# Sheet1.net
KiCad netlist of a schematic drawn in Altium Designer
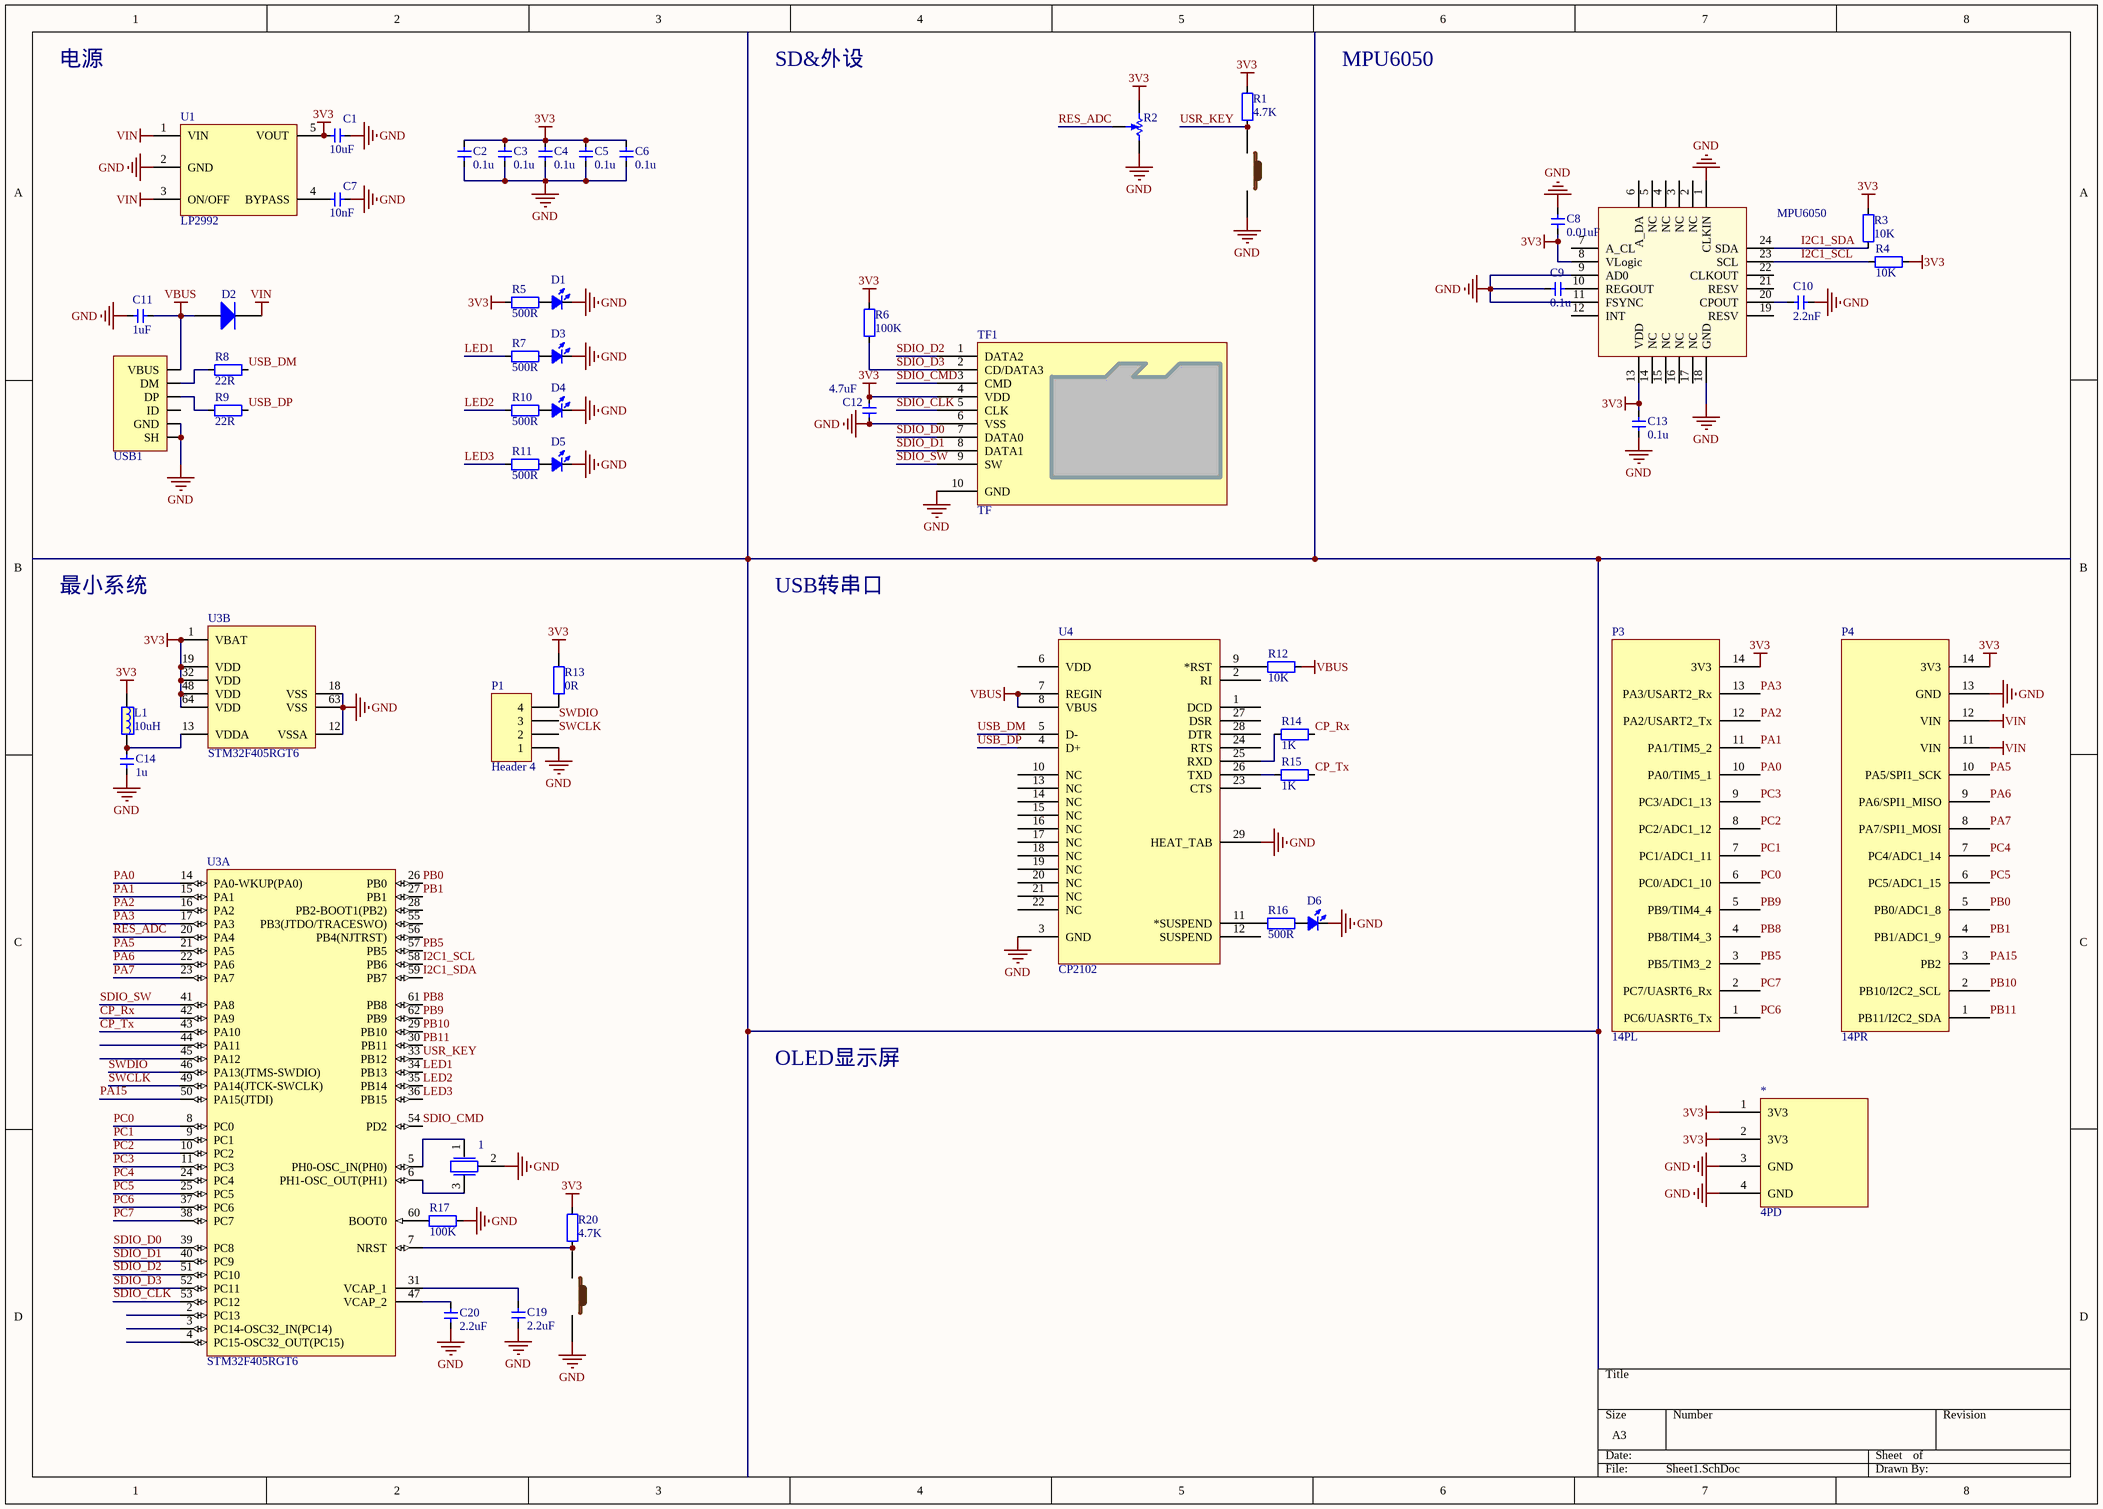
[diagram p0: Sheet1.SchDoc]

(export (version "E")
  (design (tool "Eeschema 10.0.6"))
  (components
    (comp (ref "*") (value "4PD") (footprint "4P") (libsource (lib "mLib") (part "4PD")))
    (comp (ref "1")
      (value "晶振-3Pin")
      (footprint "晶振-3P")
      (description "村田贴片")
      (libsource (lib "mLib") (part "晶振-3Pin"))
    )
    (comp (ref "C1")
      (value "10uF")
      (footprint "mLib:0603-CAP")
      (description "Capacitor")
      (libsource (lib "mLib") (part "电容-0603"))
    )
    (comp (ref "C2")
      (value "0.1u")
      (footprint "mLib:0603-CAP")
      (description "Capacitor")
      (fields (field (name "Comment") "0.1uF"))
      (libsource (lib "mLib") (part "电容-0603"))
    )
    (comp (ref "C3")
      (value "0.1u")
      (footprint "mLib:0603-CAP")
      (description "Capacitor")
      (fields (field (name "Comment") "0.1uF"))
      (libsource (lib "mLib") (part "电容-0603"))
    )
    (comp (ref "C4")
      (value "0.1u")
      (footprint "mLib:0603-CAP")
      (description "Capacitor")
      (fields (field (name "Comment") "0.1uF"))
      (libsource (lib "mLib") (part "电容-0603"))
    )
    (comp (ref "C5")
      (value "0.1u")
      (footprint "mLib:0603-CAP")
      (description "Capacitor")
      (fields (field (name "Comment") "电容-0603"))
      (libsource (lib "mLib") (part "电容-0603"))
    )
    (comp (ref "C6")
      (value "0.1u")
      (footprint "mLib:0603-CAP")
      (description "Capacitor")
      (fields (field (name "Comment") "0.1uF"))
      (libsource (lib "mLib") (part "电容-0603"))
    )
    (comp (ref "C7")
      (value "10nF")
      (footprint "mLib:0603-CAP")
      (description "Capacitor")
      (libsource (lib "mLib") (part "电容-0603"))
    )
    (comp (ref "C8")
      (value "0.01uF")
      (footprint "mLib:0603-CAP")
      (description "Capacitor")
      (libsource (lib "mLib") (part "电容-0603"))
    )
    (comp (ref "C9")
      (value "0.1u")
      (footprint "mLib:0603-CAP")
      (description "Capacitor")
      (fields (field (name "Comment") "0.1uF"))
      (libsource (lib "mLib") (part "电容-0603"))
    )
    (comp (ref "C10")
      (value "2.2nF")
      (footprint "mLib:0603-CAP")
      (description "Capacitor")
      (libsource (lib "mLib") (part "电容-0603"))
    )
    (comp (ref "C11")
      (value "1uF")
      (footprint "mLib:0603-CAP")
      (description "Capacitor")
      (libsource (lib "mLib") (part "电容-0603"))
    )
    (comp (ref "C12")
      (value "4.7uF")
      (footprint "mLib:0603-CAP")
      (description "Capacitor")
      (libsource (lib "mLib") (part "电容-0603"))
    )
    (comp (ref "C13")
      (value "0.1u")
      (footprint "mLib:0603-CAP")
      (description "Capacitor")
      (fields (field (name "Comment") "0.1uF"))
      (libsource (lib "mLib") (part "电容-0603"))
    )
    (comp (ref "C14")
      (value "1u")
      (footprint "mLib:0603-CAP")
      (description "Capacitor")
      (fields (field (name "Comment") "1uF"))
      (libsource (lib "mLib") (part "电容-0603"))
    )
    (comp (ref "C19")
      (value "2.2uF")
      (footprint "mLib:0603-CAP")
      (description "Capacitor")
      (libsource (lib "mLib") (part "电容-0603"))
    )
    (comp (ref "C20")
      (value "2.2uF")
      (footprint "mLib:0603-CAP")
      (description "Capacitor")
      (libsource (lib "mLib") (part "电容-0603"))
    )
    (comp (ref "D1")
      (value "LED-0603")
      (footprint "mLib:0603-LED-BLUE")
      (description "LED")
      (libsource (lib "mLib") (part "LED-0603"))
    )
    (comp (ref "D2")
      (value "二极管-5819W")
      (footprint "SOD-123")
      (description "40V")
      (libsource (lib "mLib") (part "二极管-5819W"))
    )
    (comp (ref "D3")
      (value "LED-0603")
      (footprint "mLib:0603-LED-BLUE")
      (description "LED")
      (libsource (lib "mLib") (part "LED-0603"))
    )
    (comp (ref "D4")
      (value "LED-0603")
      (footprint "mLib:0603-LED-BLUE")
      (description "LED")
      (libsource (lib "mLib") (part "LED-0603"))
    )
    (comp (ref "D5")
      (value "LED-0603")
      (footprint "mLib:0603-LED-BLUE")
      (description "LED")
      (libsource (lib "mLib") (part "LED-0603"))
    )
    (comp (ref "D6")
      (value "LED-0603")
      (footprint "mLib:0603-LED-BLUE")
      (description "LED")
      (libsource (lib "mLib") (part "LED-0603"))
    )
    (comp (ref "L1")
      (value "10uH")
      (footprint "0805-L")
      (description "磁珠")
      (libsource (lib "mLib") (part "电感-0805"))
    )
    (comp (ref "P1")
      (value "Header 4")
      (footprint "HDR1X4")
      (description "Header, 4-Pin")
      (fields (field (name "PUBLISHER") "Altium Limited"))
      (libsource (lib "Miscellaneous Connectors") (part "Header 4"))
    )
    (comp (ref "P3") (value "14PL") (footprint "14P") (libsource (lib "mLib") (part "14PL")))
    (comp (ref "P4") (value "14PR") (footprint "14P") (libsource (lib "mLib") (part "14PR")))
    (comp (ref "R1")
      (value "4.7K")
      (footprint "mLib:0603-RES")
      (description "Resistor")
      (libsource (lib "mLib") (part "电阻-0603"))
    )
    (comp (ref "R2")
      (value "电位器-贴片")
      (footprint "贴片电位器 3*3")
      (fields (field (name "PUBLISHER") "Altium Limited"))
      (libsource (lib "mLib") (part "电位器-贴片"))
    )
    (comp (ref "R3")
      (value "10K")
      (footprint "mLib:0603-RES")
      (description "Resistor")
      (libsource (lib "mLib") (part "电阻-0603"))
    )
    (comp (ref "R4")
      (value "10K")
      (footprint "mLib:0603-RES")
      (description "Resistor")
      (libsource (lib "") (part "电阻-0603_1"))
    )
    (comp (ref "R5")
      (value "500R")
      (footprint "mLib:0603-RES")
      (description "Resistor")
      (libsource (lib "") (part "电阻-0603_1"))
    )
    (comp (ref "R6")
      (value "100K")
      (footprint "mLib:0603-RES")
      (description "Resistor")
      (libsource (lib "mLib") (part "电阻-0603"))
    )
    (comp (ref "R7")
      (value "500R")
      (footprint "mLib:0603-RES")
      (description "Resistor")
      (libsource (lib "") (part "电阻-0603_1"))
    )
    (comp (ref "R8")
      (value "22R")
      (footprint "mLib:0603-RES")
      (description "Resistor")
      (libsource (lib "") (part "电阻-0603_1"))
    )
    (comp (ref "R9")
      (value "22R")
      (footprint "mLib:0603-RES")
      (description "Resistor")
      (libsource (lib "") (part "电阻-0603_1"))
    )
    (comp (ref "R10")
      (value "500R")
      (footprint "mLib:0603-RES")
      (description "Resistor")
      (libsource (lib "") (part "电阻-0603_1"))
    )
    (comp (ref "R11")
      (value "500R")
      (footprint "mLib:0603-RES")
      (description "Resistor")
      (libsource (lib "") (part "电阻-0603_1"))
    )
    (comp (ref "R12")
      (value "10K")
      (footprint "mLib:0603-RES")
      (description "Resistor")
      (libsource (lib "") (part "电阻-0603_1"))
    )
    (comp (ref "R13")
      (value "0R")
      (footprint "0402-0R")
      (description "Resistor")
      (fields (field (name "Comment") "电阻-0R") (field (name "PUBLISHER") "Altium Limited"))
      (libsource (lib "mLib") (part "电阻-0R"))
    )
    (comp (ref "R14")
      (value "1K")
      (footprint "mLib:0603-RES")
      (description "Resistor")
      (libsource (lib "") (part "电阻-0603_1"))
    )
    (comp (ref "R15")
      (value "1K")
      (footprint "mLib:0603-RES")
      (description "Resistor")
      (libsource (lib "") (part "电阻-0603_1"))
    )
    (comp (ref "R16")
      (value "500R")
      (footprint "mLib:0603-RES")
      (description "Resistor")
      (libsource (lib "") (part "电阻-0603_1"))
    )
    (comp (ref "R17")
      (value "100K")
      (footprint "mLib:0603-RES")
      (description "Resistor")
      (libsource (lib "") (part "电阻-0603_1"))
    )
    (comp (ref "R20")
      (value "4.7K")
      (footprint "mLib:0603-RES")
      (description "Resistor")
      (libsource (lib "mLib") (part "电阻-0603"))
    )
    (comp (ref "TF1")
      (value "TF")
      (footprint "TF-SOCKET")
      (description "8脚自弹")
      (libsource (lib "mLib") (part "TF卡座"))
    )
    (comp (ref "U1")
      (value "LP2992")
      (footprint "SOT23-5")
      (description "LDO")
      (libsource (lib "mLib") (part "LP2992"))
    )
    (comp (ref "U2")
      (value "MPU6050")
      (footprint "QFN-24")
      (description "六轴传感器")
      (libsource (lib "mLib") (part "MPU6050"))
    )
    (comp (ref "U3")
      (value "STM32F405RGT6")
      (footprint "LQFP-64_N")
      (description "MCU+FPU")
      (libsource (lib "mLib") (part "STM32F405RGT6"))
    )
    (comp (ref "U4")
      (value "CP2102")
      (footprint "QFN-28")
      (description "USB转TTL")
      (libsource (lib "mLib") (part "CP2102"))
    )
    (comp (ref "USB1")
      (value "USB-Micro")
      (footprint "mLib:USB_Micro-AB")
      (description "USB")
      (libsource (lib "mLib") (part "USB-Micro"))
    )
    (comp (ref "按键1")
      (value "Reset")
      (footprint "SW-KEY2")
      (description "贴片轻触")
      (libsource (lib "mLib") (part "按键-4Pin"))
    )
    (comp (ref "按键2")
      (value "Reset")
      (footprint "SW-KEY2")
      (description "贴片轻触")
      (libsource (lib "mLib") (part "按键-4Pin"))
    )
  )
  (nets
    (net (code "1") (name "/CP_Rx") (class "Default")
      (node (ref "R14") (pin "2") (pinfunction "2_2") (pintype "passive"))
      (node (ref "U3") (pin "42") (pinfunction "PA9_42") (pintype "bidirectional"))
    )
    (net (code "2") (name "/CP_Tx") (class "Default")
      (node (ref "R15") (pin "2") (pinfunction "2_2") (pintype "passive"))
      (node (ref "U3") (pin "43") (pinfunction "PA10_43") (pintype "bidirectional"))
    )
    (net (code "3") (name "/I2C1_SCL") (class "Default")
      (node (ref "R4") (pin "1") (pinfunction "1_1") (pintype "passive"))
      (node (ref "U2") (pin "23") (pinfunction "SCL_23") (pintype "passive"))
      (node (ref "U3") (pin "58") (pinfunction "PB6_58") (pintype "bidirectional"))
    )
    (net (code "4") (name "/I2C1_SDA") (class "Default")
      (node (ref "R3") (pin "1") (pinfunction "1_1") (pintype "passive"))
      (node (ref "U2") (pin "24") (pinfunction "SDA_24") (pintype "passive"))
      (node (ref "U3") (pin "59") (pinfunction "PB7_59") (pintype "bidirectional"))
    )
    (net (code "5") (name "/LED1") (class "Default")
      (node (ref "R7") (pin "1") (pinfunction "1_1") (pintype "passive"))
      (node (ref "U3") (pin "34") (pinfunction "PB13_34") (pintype "bidirectional"))
    )
    (net (code "6") (name "/LED2") (class "Default")
      (node (ref "R10") (pin "1") (pinfunction "1_1") (pintype "passive"))
      (node (ref "U3") (pin "35") (pinfunction "PB14_35") (pintype "bidirectional"))
    )
    (net (code "7") (name "/LED3") (class "Default")
      (node (ref "R11") (pin "1") (pinfunction "1_1") (pintype "passive"))
      (node (ref "U3") (pin "36") (pinfunction "PB15_36") (pintype "bidirectional"))
    )
    (net (code "8") (name "/PA0") (class "Default")
      (node (ref "P3") (pin "10") (pinfunction "PA0/TIM5_1_10") (pintype "passive"))
      (node (ref "U3") (pin "14") (pinfunction "PA0-WKUP(PA0)_14") (pintype "bidirectional"))
    )
    (net (code "9") (name "/PA1") (class "Default")
      (node (ref "P3") (pin "11") (pinfunction "PA1/TIM5_2_11") (pintype "passive"))
      (node (ref "U3") (pin "15") (pinfunction "PA1_15") (pintype "bidirectional"))
    )
    (net (code "10") (name "/PA2") (class "Default")
      (node (ref "P3") (pin "12") (pinfunction "PA2/USART2_Tx_12") (pintype "passive"))
      (node (ref "U3") (pin "16") (pinfunction "PA2_16") (pintype "bidirectional"))
    )
    (net (code "11") (name "/PA3") (class "Default")
      (node (ref "P3") (pin "13") (pinfunction "PA3/USART2_Rx_13") (pintype "passive"))
      (node (ref "U3") (pin "17") (pinfunction "PA3_17") (pintype "bidirectional"))
    )
    (net (code "12") (name "/PA5") (class "Default")
      (node (ref "P4") (pin "10") (pinfunction "PA5/SPI1_SCK_10") (pintype "passive"))
      (node (ref "U3") (pin "21") (pinfunction "PA5_21") (pintype "bidirectional"))
    )
    (net (code "13") (name "/PA6") (class "Default")
      (node (ref "P4") (pin "9") (pinfunction "PA6/SPI1_MISO_9") (pintype "passive"))
      (node (ref "U3") (pin "22") (pinfunction "PA6_22") (pintype "bidirectional"))
    )
    (net (code "14") (name "/PA7") (class "Default")
      (node (ref "P4") (pin "8") (pinfunction "PA7/SPI1_MOSI_8") (pintype "passive"))
      (node (ref "U3") (pin "23") (pinfunction "PA7_23") (pintype "bidirectional"))
    )
    (net (code "15") (name "/PA15") (class "Default")
      (node (ref "P4") (pin "3") (pinfunction "PB2_3") (pintype "passive"))
      (node (ref "U3") (pin "50") (pinfunction "PA15(JTDI)_50") (pintype "bidirectional"))
    )
    (net (code "16") (name "/PB0") (class "Default")
      (node (ref "P4") (pin "5") (pinfunction "PB0/ADC1_8_5") (pintype "passive"))
      (node (ref "U3") (pin "26") (pinfunction "PB0_26") (pintype "bidirectional"))
    )
    (net (code "17") (name "/PB1") (class "Default")
      (node (ref "P4") (pin "4") (pinfunction "PB1/ADC1_9_4") (pintype "passive"))
      (node (ref "U3") (pin "27") (pinfunction "PB1_27") (pintype "bidirectional"))
    )
    (net (code "18") (name "/PB5") (class "Default")
      (node (ref "P3") (pin "3") (pinfunction "PB5/TIM3_2_3") (pintype "passive"))
      (node (ref "U3") (pin "57") (pinfunction "PB5_57") (pintype "bidirectional"))
    )
    (net (code "19") (name "/PB8") (class "Default")
      (node (ref "P3") (pin "4") (pinfunction "PB8/TIM4_3_4") (pintype "passive"))
      (node (ref "U3") (pin "61") (pinfunction "PB8_61") (pintype "bidirectional"))
    )
    (net (code "20") (name "/PB9") (class "Default")
      (node (ref "P3") (pin "5") (pinfunction "PB9/TIM4_4_5") (pintype "passive"))
      (node (ref "U3") (pin "62") (pinfunction "PB9_62") (pintype "bidirectional"))
    )
    (net (code "21") (name "/PB10") (class "Default")
      (node (ref "P4") (pin "2") (pinfunction "PB10/I2C2_SCL_2") (pintype "passive"))
      (node (ref "U3") (pin "29") (pinfunction "PB10_29") (pintype "bidirectional"))
    )
    (net (code "22") (name "/PB11") (class "Default")
      (node (ref "P4") (pin "1") (pinfunction "PB11/I2C2_SDA_1") (pintype "passive"))
      (node (ref "U3") (pin "30") (pinfunction "PB11_30") (pintype "bidirectional"))
    )
    (net (code "23") (name "/PC0") (class "Default")
      (node (ref "P3") (pin "6") (pinfunction "PC0/ADC1_10_6") (pintype "passive"))
      (node (ref "U3") (pin "8") (pinfunction "PC0_8") (pintype "bidirectional"))
    )
    (net (code "24") (name "/PC1") (class "Default")
      (node (ref "P3") (pin "7") (pinfunction "PC1/ADC1_11_7") (pintype "passive"))
      (node (ref "U3") (pin "9") (pinfunction "PC1_9") (pintype "bidirectional"))
    )
    (net (code "25") (name "/PC2") (class "Default")
      (node (ref "P3") (pin "8") (pinfunction "PC2/ADC1_12_8") (pintype "passive"))
      (node (ref "U3") (pin "10") (pinfunction "PC2_10") (pintype "bidirectional"))
    )
    (net (code "26") (name "/PC3") (class "Default")
      (node (ref "P3") (pin "9") (pinfunction "PC3/ADC1_13_9") (pintype "passive"))
      (node (ref "U3") (pin "11") (pinfunction "PC3_11") (pintype "bidirectional"))
    )
    (net (code "27") (name "/PC4") (class "Default")
      (node (ref "P4") (pin "7") (pinfunction "PC4/ADC1_14_7") (pintype "passive"))
      (node (ref "U3") (pin "24") (pinfunction "PC4_24") (pintype "bidirectional"))
    )
    (net (code "28") (name "/PC5") (class "Default")
      (node (ref "P4") (pin "6") (pinfunction "PC5/ADC1_15_6") (pintype "passive"))
      (node (ref "U3") (pin "25") (pinfunction "PC5_25") (pintype "bidirectional"))
    )
    (net (code "29") (name "/PC6") (class "Default")
      (node (ref "P3") (pin "1") (pinfunction "PC6/UASRT6_Tx_1") (pintype "passive"))
      (node (ref "U3") (pin "37") (pinfunction "PC6_37") (pintype "bidirectional"))
    )
    (net (code "30") (name "/PC7") (class "Default")
      (node (ref "P3") (pin "2") (pinfunction "PC7/UASRT6_Rx_2") (pintype "passive"))
      (node (ref "U3") (pin "38") (pinfunction "PC7_38") (pintype "bidirectional"))
    )
    (net (code "31") (name "/RES_ADC") (class "Default")
      (node (ref "R2") (pin "3") (pinfunction "W_3") (pintype "passive"))
      (node (ref "U3") (pin "20") (pinfunction "PA4_20") (pintype "bidirectional"))
    )
    (net (code "32") (name "/SDIO_CLK") (class "Default")
      (node (ref "TF1") (pin "5") (pinfunction "CLK_5") (pintype "passive"))
      (node (ref "U3") (pin "53") (pinfunction "PC12_53") (pintype "bidirectional"))
    )
    (net (code "33") (name "/SDIO_CMD") (class "Default")
      (node (ref "TF1") (pin "3") (pinfunction "CMD_3") (pintype "passive"))
      (node (ref "U3") (pin "54") (pinfunction "PD2_54") (pintype "bidirectional"))
    )
    (net (code "34") (name "/SDIO_D0") (class "Default")
      (node (ref "TF1") (pin "7") (pinfunction "DATA0_7") (pintype "passive"))
      (node (ref "U3") (pin "39") (pinfunction "PC8_39") (pintype "bidirectional"))
    )
    (net (code "35") (name "/SDIO_D1") (class "Default")
      (node (ref "TF1") (pin "8") (pinfunction "DATA1_8") (pintype "passive"))
      (node (ref "U3") (pin "40") (pinfunction "PC9_40") (pintype "bidirectional"))
    )
    (net (code "36") (name "/SDIO_D2") (class "Default")
      (node (ref "TF1") (pin "1") (pinfunction "DATA2_1") (pintype "passive"))
      (node (ref "U3") (pin "51") (pinfunction "PC10_51") (pintype "bidirectional"))
    )
    (net (code "37") (name "/SDIO_D3") (class "Default")
      (node (ref "R6") (pin "1") (pinfunction "1_1") (pintype "passive"))
      (node (ref "TF1") (pin "2") (pinfunction "CD/DATA3_2") (pintype "passive"))
      (node (ref "U3") (pin "52") (pinfunction "PC11_52") (pintype "bidirectional"))
    )
    (net (code "38") (name "/SDIO_SW") (class "Default")
      (node (ref "TF1") (pin "9") (pinfunction "SW_9") (pintype "passive"))
      (node (ref "U3") (pin "41") (pinfunction "PA8_41") (pintype "bidirectional"))
    )
    (net (code "39") (name "/SWCLK") (class "Default")
      (node (ref "P1") (pin "2") (pinfunction "2_2") (pintype "passive"))
      (node (ref "U3") (pin "49") (pinfunction "PA14(JTCK-SWCLK)_49") (pintype "bidirectional"))
    )
    (net (code "40") (name "/SWDIO") (class "Default")
      (node (ref "P1") (pin "3") (pinfunction "3_3") (pintype "passive"))
      (node (ref "U3") (pin "46") (pinfunction "PA13(JTMS-SWDIO)_46") (pintype "bidirectional"))
    )
    (net (code "41") (name "/USB_DM") (class "Default")
      (node (ref "R8") (pin "2") (pinfunction "2_2") (pintype "passive"))
      (node (ref "U4") (pin "5") (pinfunction "D-_5") (pintype "passive"))
    )
    (net (code "42") (name "/USB_DP") (class "Default")
      (node (ref "R9") (pin "2") (pinfunction "2_2") (pintype "passive"))
      (node (ref "U4") (pin "4") (pinfunction "D+_4") (pintype "passive"))
    )
    (net (code "43") (name "/USR_KEY") (class "Default")
      (node (ref "R1") (pin "1") (pinfunction "1_1") (pintype "passive"))
      (node (ref "U3") (pin "33") (pinfunction "PB12_33") (pintype "bidirectional"))
      (node (ref "按键1") (pin "1") (pinfunction "1_1") (pintype "passive"))
    )
    (net (code "44") (name "3V3") (class "Default")
      (node (ref "*") (pin "1") (pinfunction "3V3_1") (pintype "passive"))
      (node (ref "*") (pin "2") (pinfunction "3V3_2") (pintype "passive"))
      (node (ref "C1") (pin "2") (pinfunction "2_2") (pintype "passive"))
      (node (ref "C12") (pin "1") (pinfunction "1_1") (pintype "passive"))
      (node (ref "C13") (pin "2") (pinfunction "2_2") (pintype "passive"))
      (node (ref "C2") (pin "1") (pinfunction "1_1") (pintype "passive"))
      (node (ref "C3") (pin "1") (pinfunction "1_1") (pintype "passive"))
      (node (ref "C4") (pin "1") (pinfunction "1_1") (pintype "passive"))
      (node (ref "C5") (pin "1") (pinfunction "1_1") (pintype "passive"))
      (node (ref "C6") (pin "1") (pinfunction "1_1") (pintype "passive"))
      (node (ref "C8") (pin "2") (pinfunction "2_2") (pintype "passive"))
      (node (ref "L1") (pin "1") (pintype "passive"))
      (node (ref "P3") (pin "14") (pinfunction "3V3_14") (pintype "passive"))
      (node (ref "P4") (pin "14") (pinfunction "3V3_14") (pintype "passive"))
      (node (ref "R1") (pin "2") (pinfunction "2_2") (pintype "passive"))
      (node (ref "R13") (pin "2") (pinfunction "2_2") (pintype "passive"))
      (node (ref "R2") (pin "2") (pinfunction "-_2") (pintype "passive"))
      (node (ref "R20") (pin "2") (pinfunction "2_2") (pintype "passive"))
      (node (ref "R3") (pin "2") (pinfunction "2_2") (pintype "passive"))
      (node (ref "R4") (pin "2") (pinfunction "2_2") (pintype "passive"))
      (node (ref "R5") (pin "1") (pinfunction "1_1") (pintype "passive"))
      (node (ref "R6") (pin "2") (pinfunction "2_2") (pintype "passive"))
      (node (ref "TF1") (pin "4") (pinfunction "VDD_4") (pintype "passive"))
      (node (ref "U1") (pin "5") (pinfunction "VOUT_5") (pintype "passive"))
      (node (ref "U2") (pin "13") (pinfunction "VDD_13") (pintype "passive"))
      (node (ref "U2") (pin "8") (pinfunction "VLogic_8") (pintype "passive"))
      (node (ref "U3") (pin "1") (pinfunction "VBAT_1") (pintype "power_in"))
      (node (ref "U3") (pin "19") (pinfunction "VDD_19") (pintype "power_in"))
      (node (ref "U3") (pin "32") (pinfunction "VDD_32") (pintype "power_in"))
      (node (ref "U3") (pin "48") (pinfunction "VDD_48") (pintype "power_in"))
      (node (ref "U3") (pin "64") (pinfunction "VDD_64") (pintype "power_in"))
    )
    (net (code "45") (name "GND") (class "Default")
      (node (ref "*") (pin "3") (pinfunction "GND_3") (pintype "passive"))
      (node (ref "*") (pin "4") (pinfunction "GND_4") (pintype "passive"))
      (node (ref "1") (pin "2") (pinfunction "2_2") (pintype "passive"))
      (node (ref "C1") (pin "1") (pinfunction "1_1") (pintype "passive"))
      (node (ref "C10") (pin "2") (pinfunction "2_2") (pintype "passive"))
      (node (ref "C11") (pin "1") (pinfunction "1_1") (pintype "passive"))
      (node (ref "C12") (pin "2") (pinfunction "2_2") (pintype "passive"))
      (node (ref "C13") (pin "1") (pinfunction "1_1") (pintype "passive"))
      (node (ref "C14") (pin "1") (pinfunction "1_1") (pintype "passive"))
      (node (ref "C19") (pin "1") (pinfunction "1_1") (pintype "passive"))
      (node (ref "C2") (pin "2") (pinfunction "2_2") (pintype "passive"))
      (node (ref "C20") (pin "1") (pinfunction "1_1") (pintype "passive"))
      (node (ref "C3") (pin "2") (pinfunction "2_2") (pintype "passive"))
      (node (ref "C4") (pin "2") (pinfunction "2_2") (pintype "passive"))
      (node (ref "C5") (pin "2") (pinfunction "2_2") (pintype "passive"))
      (node (ref "C6") (pin "2") (pinfunction "2_2") (pintype "passive"))
      (node (ref "C7") (pin "1") (pinfunction "1_1") (pintype "passive"))
      (node (ref "C8") (pin "1") (pinfunction "1_1") (pintype "passive"))
      (node (ref "C9") (pin "1") (pinfunction "1_1") (pintype "passive"))
      (node (ref "D1") (pin "2") (pinfunction "K_2") (pintype "passive"))
      (node (ref "D3") (pin "2") (pinfunction "K_2") (pintype "passive"))
      (node (ref "D4") (pin "2") (pinfunction "K_2") (pintype "passive"))
      (node (ref "D5") (pin "2") (pinfunction "K_2") (pintype "passive"))
      (node (ref "D6") (pin "2") (pinfunction "K_2") (pintype "passive"))
      (node (ref "P1") (pin "1") (pinfunction "1_1") (pintype "passive"))
      (node (ref "P4") (pin "13") (pinfunction "GND_13") (pintype "passive"))
      (node (ref "R17") (pin "2") (pinfunction "2_2") (pintype "passive"))
      (node (ref "R2") (pin "1") (pinfunction "+_1") (pintype "passive"))
      (node (ref "TF1") (pin "10") (pinfunction "GND_10") (pintype "passive"))
      (node (ref "TF1") (pin "6") (pinfunction "VSS_6") (pintype "passive"))
      (node (ref "U1") (pin "2") (pinfunction "GND_2") (pintype "passive"))
      (node (ref "U2") (pin "1") (pinfunction "CLKIN_1") (pintype "passive"))
      (node (ref "U2") (pin "11") (pinfunction "FSYNC_11") (pintype "passive"))
      (node (ref "U2") (pin "18") (pinfunction "GND_18") (pintype "passive"))
      (node (ref "U2") (pin "9") (pinfunction "AD0_9") (pintype "passive"))
      (node (ref "U3") (pin "12") (pinfunction "VSSA_12") (pintype "power_in"))
      (node (ref "U3") (pin "18") (pinfunction "VSS_18") (pintype "power_in"))
      (node (ref "U3") (pin "63") (pinfunction "VSS_63") (pintype "power_in"))
      (node (ref "U4") (pin "29") (pinfunction "HEAT_TAB_29") (pintype "passive"))
      (node (ref "U4") (pin "3") (pinfunction "GND_3") (pintype "passive"))
      (node (ref "USB1") (pin "0") (pinfunction "SH_0") (pintype "passive"))
      (node (ref "USB1") (pin "5") (pinfunction "GND_5") (pintype "passive"))
      (node (ref "按键1") (pin "2") (pinfunction "2_2") (pintype "passive"))
      (node (ref "按键2") (pin "2") (pinfunction "2_2") (pintype "passive"))
    )
    (net (code "46") (name "Net-(D1-A)") (class "Default")
      (node (ref "D1") (pin "1") (pinfunction "A_1") (pintype "passive"))
      (node (ref "R5") (pin "2") (pinfunction "2_2") (pintype "passive"))
    )
    (net (code "47") (name "Net-(D3-A)") (class "Default")
      (node (ref "D3") (pin "1") (pinfunction "A_1") (pintype "passive"))
      (node (ref "R7") (pin "2") (pinfunction "2_2") (pintype "passive"))
    )
    (net (code "48") (name "Net-(D4-A)") (class "Default")
      (node (ref "D4") (pin "1") (pinfunction "A_1") (pintype "passive"))
      (node (ref "R10") (pin "2") (pinfunction "2_2") (pintype "passive"))
    )
    (net (code "49") (name "Net-(D5-A)") (class "Default")
      (node (ref "D5") (pin "1") (pinfunction "A_1") (pintype "passive"))
      (node (ref "R11") (pin "2") (pinfunction "2_2") (pintype "passive"))
    )
    (net (code "50") (name "Net-(D6-A)") (class "Default")
      (node (ref "D6") (pin "1") (pinfunction "A_1") (pintype "passive"))
      (node (ref "R16") (pin "2") (pinfunction "2_2") (pintype "passive"))
    )
    (net (code "51") (name "Net-(P1-Pad4)") (class "Default")
      (node (ref "P1") (pin "4") (pinfunction "4_4") (pintype "passive"))
      (node (ref "R13") (pin "1") (pinfunction "1_1") (pintype "passive"))
    )
    (net (code "52") (name "Net-(U1-BYPASS)") (class "Default")
      (node (ref "C7") (pin "2") (pinfunction "2_2") (pintype "passive"))
      (node (ref "U1") (pin "4") (pinfunction "BYPASS_4") (pintype "passive"))
    )
    (net (code "53") (name "Net-(U2-CPOUT)") (class "Default")
      (node (ref "C10") (pin "1") (pinfunction "1_1") (pintype "passive"))
      (node (ref "U2") (pin "20") (pinfunction "CPOUT_20") (pintype "passive"))
    )
    (net (code "54") (name "Net-(U2-REGOUT)") (class "Default")
      (node (ref "C9") (pin "2") (pinfunction "2_2") (pintype "passive"))
      (node (ref "U2") (pin "10") (pinfunction "REGOUT_10") (pintype "passive"))
    )
    (net (code "55") (name "Net-(U3A-BOOT0)") (class "Default")
      (node (ref "R17") (pin "1") (pinfunction "1_1") (pintype "passive"))
      (node (ref "U3") (pin "60") (pinfunction "BOOT0_60") (pintype "input"))
    )
    (net (code "56") (name "Net-(U3A-NRST)") (class "Default")
      (node (ref "R20") (pin "1") (pinfunction "1_1") (pintype "passive"))
      (node (ref "U3") (pin "7") (pinfunction "NRST_7") (pintype "bidirectional"))
      (node (ref "按键2") (pin "1") (pinfunction "1_1") (pintype "passive"))
    )
    (net (code "57") (name "Net-(U3A-PH0-OSC_IN(PH0))") (class "Default")
      (node (ref "1") (pin "1") (pinfunction "1_1") (pintype "passive"))
      (node (ref "U3") (pin "5") (pinfunction "PH0-OSC_IN(PH0)_5") (pintype "bidirectional"))
    )
    (net (code "58") (name "Net-(U3A-PH1-OSC_OUT(PH1))") (class "Default")
      (node (ref "1") (pin "3") (pinfunction "3_3") (pintype "passive"))
      (node (ref "U3") (pin "6") (pinfunction "PH1-OSC_OUT(PH1)_6") (pintype "bidirectional"))
    )
    (net (code "59") (name "Net-(U3A-VCAP_1)") (class "Default")
      (node (ref "C19") (pin "2") (pinfunction "2_2") (pintype "passive"))
      (node (ref "U3") (pin "31") (pinfunction "VCAP_1_31") (pintype "power_in"))
    )
    (net (code "60") (name "Net-(U3A-VCAP_2)") (class "Default")
      (node (ref "C20") (pin "2") (pinfunction "2_2") (pintype "passive"))
      (node (ref "U3") (pin "47") (pinfunction "VCAP_2_47") (pintype "power_in"))
    )
    (net (code "61") (name "Net-(U3B-VDDA)") (class "Default")
      (node (ref "C14") (pin "2") (pinfunction "2_2") (pintype "passive"))
      (node (ref "L1") (pin "2") (pinfunction "2_2") (pintype "passive"))
      (node (ref "U3") (pin "13") (pinfunction "VDDA_13") (pintype "power_in"))
    )
    (net (code "62") (name "Net-(U4-*RST)") (class "Default")
      (node (ref "R12") (pin "1") (pinfunction "1_1") (pintype "passive"))
      (node (ref "U4") (pin "9") (pinfunction "*RST_9") (pintype "passive"))
    )
    (net (code "63") (name "Net-(U4-*SUSPEND)") (class "Default")
      (node (ref "R16") (pin "1") (pinfunction "1_1") (pintype "passive"))
      (node (ref "U4") (pin "11") (pinfunction "*SUSPEND_11") (pintype "passive"))
    )
    (net (code "64") (name "Net-(U4-RXD)") (class "Default")
      (node (ref "R14") (pin "1") (pinfunction "1_1") (pintype "passive"))
      (node (ref "U4") (pin "25") (pinfunction "RXD_25") (pintype "passive"))
    )
    (net (code "65") (name "Net-(U4-TXD)") (class "Default")
      (node (ref "R15") (pin "1") (pinfunction "1_1") (pintype "passive"))
      (node (ref "U4") (pin "26") (pinfunction "TXD_26") (pintype "passive"))
    )
    (net (code "66") (name "Net-(USB1-DM)") (class "Default")
      (node (ref "R8") (pin "1") (pinfunction "1_1") (pintype "passive"))
      (node (ref "USB1") (pin "2") (pinfunction "DM_2") (pintype "passive"))
    )
    (net (code "67") (name "Net-(USB1-DP)") (class "Default")
      (node (ref "R9") (pin "1") (pinfunction "1_1") (pintype "passive"))
      (node (ref "USB1") (pin "3") (pinfunction "DP_3") (pintype "passive"))
    )
    (net (code "68") (name "VBUS") (class "Default")
      (node (ref "C11") (pin "2") (pinfunction "2_2") (pintype "passive"))
      (node (ref "D2") (pin "1") (pinfunction "A_1") (pintype "passive"))
      (node (ref "R12") (pin "2") (pinfunction "2_2") (pintype "passive"))
      (node (ref "U4") (pin "7") (pinfunction "REGIN_7") (pintype "passive"))
      (node (ref "U4") (pin "8") (pinfunction "VBUS_8") (pintype "passive"))
      (node (ref "USB1") (pin "1") (pinfunction "VBUS_1") (pintype "passive"))
    )
    (net (code "69") (name "VIN") (class "Default")
      (node (ref "D2") (pin "2") (pinfunction "K_2") (pintype "passive"))
      (node (ref "P4") (pin "11") (pinfunction "VIN_11") (pintype "passive"))
      (node (ref "P4") (pin "12") (pinfunction "VIN_12") (pintype "passive"))
      (node (ref "U1") (pin "1") (pinfunction "VIN_1") (pintype "passive"))
      (node (ref "U1") (pin "3") (pinfunction "ON/OFF_3") (pintype "passive"))
    )
    (net (code "70") (name "unconnected-(U2-A_CL-Pad7)") (class "Default")
      (node (ref "U2") (pin "7") (pinfunction "A_CL_7") (pintype "passive"))
    )
    (net (code "71") (name "unconnected-(U2-A_DA-Pad6)") (class "Default")
      (node (ref "U2") (pin "6") (pinfunction "A_DA_6") (pintype "passive"))
    )
    (net (code "72") (name "unconnected-(U2-CLKOUT-Pad22)") (class "Default")
      (node (ref "U2") (pin "22") (pinfunction "CLKOUT_22") (pintype "passive"))
    )
    (net (code "73") (name "unconnected-(U2-INT-Pad12)") (class "Default")
      (node (ref "U2") (pin "12") (pinfunction "INT_12") (pintype "passive"))
    )
    (net (code "74") (name "unconnected-(U2-NC-Pad2)") (class "Default")
      (node (ref "U2") (pin "2") (pinfunction "NC_2") (pintype "passive"))
    )
    (net (code "75") (name "unconnected-(U2-NC-Pad3)") (class "Default")
      (node (ref "U2") (pin "3") (pinfunction "NC_3") (pintype "passive"))
    )
    (net (code "76") (name "unconnected-(U2-NC-Pad4)") (class "Default")
      (node (ref "U2") (pin "4") (pinfunction "NC_4") (pintype "passive"))
    )
    (net (code "77") (name "unconnected-(U2-NC-Pad5)") (class "Default")
      (node (ref "U2") (pin "5") (pinfunction "NC_5") (pintype "passive"))
    )
    (net (code "78") (name "unconnected-(U2-NC-Pad14)") (class "Default")
      (node (ref "U2") (pin "14") (pinfunction "NC_14") (pintype "passive"))
    )
    (net (code "79") (name "unconnected-(U2-NC-Pad15)") (class "Default")
      (node (ref "U2") (pin "15") (pinfunction "NC_15") (pintype "passive"))
    )
    (net (code "80") (name "unconnected-(U2-NC-Pad16)") (class "Default")
      (node (ref "U2") (pin "16") (pinfunction "NC_16") (pintype "passive"))
    )
    (net (code "81") (name "unconnected-(U2-NC-Pad17)") (class "Default")
      (node (ref "U2") (pin "17") (pinfunction "NC_17") (pintype "passive"))
    )
    (net (code "82") (name "unconnected-(U2-RESV-Pad19)") (class "Default")
      (node (ref "U2") (pin "19") (pinfunction "RESV_19") (pintype "passive"))
    )
    (net (code "83") (name "unconnected-(U2-RESV-Pad21)") (class "Default")
      (node (ref "U2") (pin "21") (pinfunction "RESV_21") (pintype "passive"))
    )
    (net (code "84") (name "unconnected-(U3A-PA11-Pad44)") (class "Default")
      (node (ref "U3") (pin "44") (pinfunction "PA11_44") (pintype "bidirectional"))
    )
    (net (code "85") (name "unconnected-(U3A-PA12-Pad45)") (class "Default")
      (node (ref "U3") (pin "45") (pinfunction "PA12_45") (pintype "bidirectional"))
    )
    (net (code "86") (name "unconnected-(U3A-PB2-BOOT1(PB2)-Pad28)") (class "Default")
      (node (ref "U3") (pin "28") (pinfunction "PB2-BOOT1(PB2)_28") (pintype "bidirectional"))
    )
    (net (code "87") (name "unconnected-(U3A-PB3(JTDO{slash}TRACESWO)-Pad55)") (class "Default")
      (node (ref "U3") (pin "55") (pinfunction "PB3(JTDO/TRACESWO)_55") (pintype "bidirectional"))
    )
    (net (code "88") (name "unconnected-(U3A-PB4(NJTRST)-Pad56)") (class "Default")
      (node (ref "U3") (pin "56") (pinfunction "PB4(NJTRST)_56") (pintype "bidirectional"))
    )
    (net (code "89") (name "unconnected-(U3A-PC13-Pad2)") (class "Default")
      (node (ref "U3") (pin "2") (pinfunction "PC13_2") (pintype "bidirectional"))
    )
    (net (code "90") (name "unconnected-(U3A-PC14-OSC32_IN(PC14)-Pad3)") (class "Default")
      (node (ref "U3") (pin "3") (pinfunction "PC14-OSC32_IN(PC14)_3") (pintype "bidirectional"))
    )
    (net (code "91") (name "unconnected-(U3A-PC15-OSC32_OUT(PC15)-Pad4)") (class "Default")
      (node (ref "U3") (pin "4") (pinfunction "PC15-OSC32_OUT(PC15)_4") (pintype "bidirectional"))
    )
    (net (code "92") (name "unconnected-(U4-CTS-Pad23)") (class "Default")
      (node (ref "U4") (pin "23") (pinfunction "CTS_23") (pintype "passive"))
    )
    (net (code "93") (name "unconnected-(U4-DCD-Pad1)") (class "Default")
      (node (ref "U4") (pin "1") (pinfunction "DCD_1") (pintype "passive"))
    )
    (net (code "94") (name "unconnected-(U4-DSR-Pad27)") (class "Default")
      (node (ref "U4") (pin "27") (pinfunction "DSR_27") (pintype "passive"))
    )
    (net (code "95") (name "unconnected-(U4-DTR-Pad28)") (class "Default")
      (node (ref "U4") (pin "28") (pinfunction "DTR_28") (pintype "passive"))
    )
    (net (code "96") (name "unconnected-(U4-NC-Pad10)") (class "Default")
      (node (ref "U4") (pin "10") (pinfunction "NC_10") (pintype "passive"))
    )
    (net (code "97") (name "unconnected-(U4-NC-Pad13)") (class "Default")
      (node (ref "U4") (pin "13") (pinfunction "NC_13") (pintype "passive"))
    )
    (net (code "98") (name "unconnected-(U4-NC-Pad14)") (class "Default")
      (node (ref "U4") (pin "14") (pinfunction "NC_14") (pintype "passive"))
    )
    (net (code "99") (name "unconnected-(U4-NC-Pad15)") (class "Default")
      (node (ref "U4") (pin "15") (pinfunction "NC_15") (pintype "passive"))
    )
    (net (code "100") (name "unconnected-(U4-NC-Pad16)") (class "Default")
      (node (ref "U4") (pin "16") (pinfunction "NC_16") (pintype "passive"))
    )
    (net (code "101") (name "unconnected-(U4-NC-Pad17)") (class "Default")
      (node (ref "U4") (pin "17") (pinfunction "NC_17") (pintype "passive"))
    )
    (net (code "102") (name "unconnected-(U4-NC-Pad18)") (class "Default")
      (node (ref "U4") (pin "18") (pinfunction "NC_18") (pintype "passive"))
    )
    (net (code "103") (name "unconnected-(U4-NC-Pad19)") (class "Default")
      (node (ref "U4") (pin "19") (pinfunction "NC_19") (pintype "passive"))
    )
    (net (code "104") (name "unconnected-(U4-NC-Pad20)") (class "Default")
      (node (ref "U4") (pin "20") (pinfunction "NC_20") (pintype "passive"))
    )
    (net (code "105") (name "unconnected-(U4-NC-Pad21)") (class "Default")
      (node (ref "U4") (pin "21") (pinfunction "NC_21") (pintype "passive"))
    )
    (net (code "106") (name "unconnected-(U4-NC-Pad22)") (class "Default")
      (node (ref "U4") (pin "22") (pinfunction "NC_22") (pintype "passive"))
    )
    (net (code "107") (name "unconnected-(U4-RI-Pad2)") (class "Default")
      (node (ref "U4") (pin "2") (pinfunction "RI_2") (pintype "passive"))
    )
    (net (code "108") (name "unconnected-(U4-RTS-Pad24)") (class "Default")
      (node (ref "U4") (pin "24") (pinfunction "RTS_24") (pintype "passive"))
    )
    (net (code "109") (name "unconnected-(U4-SUSPEND-Pad12)") (class "Default")
      (node (ref "U4") (pin "12") (pinfunction "SUSPEND_12") (pintype "passive"))
    )
    (net (code "110") (name "unconnected-(U4-VDD-Pad6)") (class "Default")
      (node (ref "U4") (pin "6") (pinfunction "VDD_6") (pintype "passive"))
    )
    (net (code "111") (name "unconnected-(USB1-ID-Pad4)") (class "Default")
      (node (ref "USB1") (pin "4") (pinfunction "ID_4") (pintype "passive"))
    )
  )
)
